# qec_pcb_v2.net
KiCad netlist of a schematic drawn in EAGLE
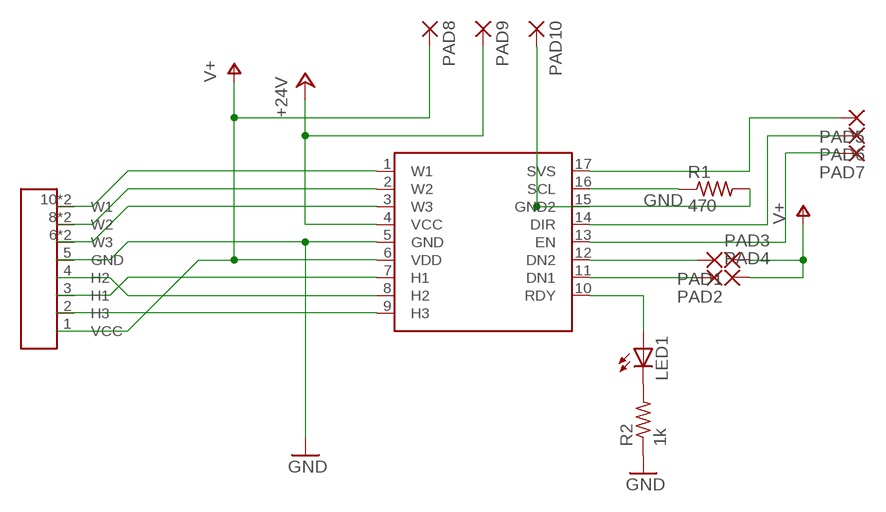
[diagram p0: schematic, sheet 1]

(export (version "E")
  (design (tool "Eeschema 10.0.6"))
  (components
    (comp (ref "K1")
      (value "68611114122")
      (footprint "eagle-import:68611114122")
      (libsource (lib "eagle-import") (part "68611114122"))
    )
    (comp (ref "LED1")
      (value "LEDCHIPLED_0805")
      (footprint "eagle-import:CHIPLED_0805")
      (libsource (lib "eagle-import") (part "LEDCHIPLED_0805"))
    )
    (comp (ref "PAD1")
      (value "SMD2")
      (footprint "eagle-import:SMD1,27-2,54")
      (libsource (lib "eagle-import") (part "SMD2"))
    )
    (comp (ref "PAD2")
      (value "SMD2")
      (footprint "eagle-import:SMD1,27-2,54")
      (libsource (lib "eagle-import") (part "SMD2"))
    )
    (comp (ref "PAD3")
      (value "SMD2")
      (footprint "eagle-import:SMD1,27-2,54")
      (libsource (lib "eagle-import") (part "SMD2"))
    )
    (comp (ref "PAD4")
      (value "SMD2")
      (footprint "eagle-import:SMD1,27-2,54")
      (libsource (lib "eagle-import") (part "SMD2"))
    )
    (comp (ref "PAD5")
      (value "SMD2")
      (footprint "eagle-import:SMD1,27-2,54")
      (libsource (lib "eagle-import") (part "SMD2"))
    )
    (comp (ref "PAD6")
      (value "SMD2")
      (footprint "eagle-import:SMD1,27-2,54")
      (libsource (lib "eagle-import") (part "SMD2"))
    )
    (comp (ref "PAD7")
      (value "SMD2")
      (footprint "eagle-import:SMD1,27-2,54")
      (libsource (lib "eagle-import") (part "SMD2"))
    )
    (comp (ref "PAD8")
      (value "SMD5")
      (footprint "eagle-import:SMD2,54-5,08")
      (libsource (lib "eagle-import") (part "SMD5"))
    )
    (comp (ref "PAD9")
      (value "SMD5")
      (footprint "eagle-import:SMD2,54-5,08")
      (libsource (lib "eagle-import") (part "SMD5"))
    )
    (comp (ref "PAD10")
      (value "SMD5")
      (footprint "eagle-import:SMD2,54-5,08")
      (libsource (lib "eagle-import") (part "SMD5"))
    )
    (comp (ref "R1")
      (value "470")
      (footprint "eagle-import:M0805")
      (libsource (lib "eagle-import") (part "R-US_M0805"))
    )
    (comp (ref "R2")
      (value "1k")
      (footprint "eagle-import:M0805")
      (libsource (lib "eagle-import") (part "R-US_M0805"))
    )
    (comp (ref "U$1")
      (value "1-Q-EC1-Q-EC-SMD")
      (footprint "eagle-import:1-Q-EC-SMD")
      (libsource (lib "eagle-import") (part "1-Q-EC1-Q-EC-SMD"))
    )
  )
  (nets
    (net (code "1") (name "+24V") (class "Default")
      (node (ref "PAD9") (pin "1") (pinfunction "P_1") (pintype "passive"))
      (node (ref "U$1") (pin "4") (pinfunction "VCC_4") (pintype "bidirectional"))
    )
    (net (code "2") (name "GND") (class "Default")
      (node (ref "K1") (pin "5") (pinfunction "GND_5") (pintype "bidirectional"))
      (node (ref "PAD10") (pin "1") (pinfunction "P_1") (pintype "passive"))
      (node (ref "R1") (pin "2") (pinfunction "2_2") (pintype "passive"))
      (node (ref "R2") (pin "1") (pinfunction "1_1") (pintype "passive"))
      (node (ref "U$1") (pin "15") (pinfunction "GND2_15") (pintype "bidirectional"))
      (node (ref "U$1") (pin "5") (pinfunction "GND_5") (pintype "bidirectional"))
    )
    (net (code "3") (name "Net-(K1-H1)") (class "Default")
      (node (ref "K1") (pin "3") (pinfunction "H1_3") (pintype "bidirectional"))
      (node (ref "U$1") (pin "7") (pinfunction "H1_7") (pintype "bidirectional"))
    )
    (net (code "4") (name "Net-(K1-H2)") (class "Default")
      (node (ref "K1") (pin "4") (pinfunction "H2_4") (pintype "bidirectional"))
      (node (ref "U$1") (pin "8") (pinfunction "H2_8") (pintype "bidirectional"))
    )
    (net (code "5") (name "Net-(K1-H3)") (class "Default")
      (node (ref "K1") (pin "2") (pinfunction "H3_2") (pintype "bidirectional"))
      (node (ref "U$1") (pin "9") (pinfunction "H3_9") (pintype "bidirectional"))
    )
    (net (code "6") (name "Net-(LED1-PadC)") (class "Default")
      (node (ref "LED1") (pin "C") (pinfunction "C_C") (pintype "passive"))
      (node (ref "R2") (pin "2") (pinfunction "2_2") (pintype "passive"))
    )
    (net (code "7") (name "Net-(PAD1-P)") (class "Default")
      (node (ref "PAD1") (pin "1") (pinfunction "P_1") (pintype "passive"))
      (node (ref "U$1") (pin "12") (pinfunction "DN2_12") (pintype "bidirectional"))
    )
    (net (code "8") (name "Net-(PAD2-P)") (class "Default")
      (node (ref "PAD2") (pin "1") (pinfunction "P_1") (pintype "passive"))
      (node (ref "U$1") (pin "11") (pinfunction "DN1_11") (pintype "bidirectional"))
    )
    (net (code "9") (name "Net-(PAD5-P)") (class "Default")
      (node (ref "PAD5") (pin "1") (pinfunction "P_1") (pintype "passive"))
      (node (ref "U$1") (pin "17") (pinfunction "SVS_17") (pintype "bidirectional"))
    )
    (net (code "10") (name "Net-(PAD6-P)") (class "Default")
      (node (ref "PAD6") (pin "1") (pinfunction "P_1") (pintype "passive"))
      (node (ref "U$1") (pin "14") (pinfunction "DIR_14") (pintype "bidirectional"))
    )
    (net (code "11") (name "Net-(PAD7-P)") (class "Default")
      (node (ref "PAD7") (pin "1") (pinfunction "P_1") (pintype "passive"))
      (node (ref "U$1") (pin "13") (pinfunction "EN_13") (pintype "bidirectional"))
    )
    (net (code "12") (name "Net-(U$1-RDY)") (class "Default")
      (node (ref "LED1") (pin "A") (pinfunction "A_A") (pintype "passive"))
      (node (ref "U$1") (pin "10") (pinfunction "RDY_10") (pintype "bidirectional"))
    )
    (net (code "13") (name "Net-(U$1-SCL)") (class "Default")
      (node (ref "R1") (pin "1") (pinfunction "1_1") (pintype "passive"))
      (node (ref "U$1") (pin "16") (pinfunction "SCL_16") (pintype "bidirectional"))
    )
    (net (code "14") (name "Net-(U$1-W1)") (class "Default")
      (node (ref "K1") (pin "10") (pinfunction "W1_10") (pintype "bidirectional"))
      (node (ref "K1") (pin "11") (pinfunction "W1_11") (pintype "bidirectional"))
      (node (ref "U$1") (pin "1") (pinfunction "W1_1") (pintype "bidirectional"))
    )
    (net (code "15") (name "Net-(U$1-W2)") (class "Default")
      (node (ref "K1") (pin "8") (pinfunction "W2_8") (pintype "bidirectional"))
      (node (ref "K1") (pin "9") (pinfunction "W2_9") (pintype "bidirectional"))
      (node (ref "U$1") (pin "2") (pinfunction "W2_2") (pintype "bidirectional"))
    )
    (net (code "16") (name "Net-(U$1-W3)") (class "Default")
      (node (ref "K1") (pin "6") (pinfunction "W3_6") (pintype "bidirectional"))
      (node (ref "K1") (pin "7") (pinfunction "W3_7") (pintype "bidirectional"))
      (node (ref "U$1") (pin "3") (pinfunction "W3_3") (pintype "bidirectional"))
    )
    (net (code "17") (name "V+") (class "Default")
      (node (ref "K1") (pin "1") (pinfunction "VCC_1") (pintype "bidirectional"))
      (node (ref "PAD3") (pin "1") (pinfunction "P_1") (pintype "passive"))
      (node (ref "PAD4") (pin "1") (pinfunction "P_1") (pintype "passive"))
      (node (ref "PAD8") (pin "1") (pinfunction "P_1") (pintype "passive"))
      (node (ref "U$1") (pin "6") (pinfunction "VDD_6") (pintype "bidirectional"))
    )
  )
)
